# SCH_Endstop_durable.net
KiCad netlist of a schematic drawn in EasyEDA
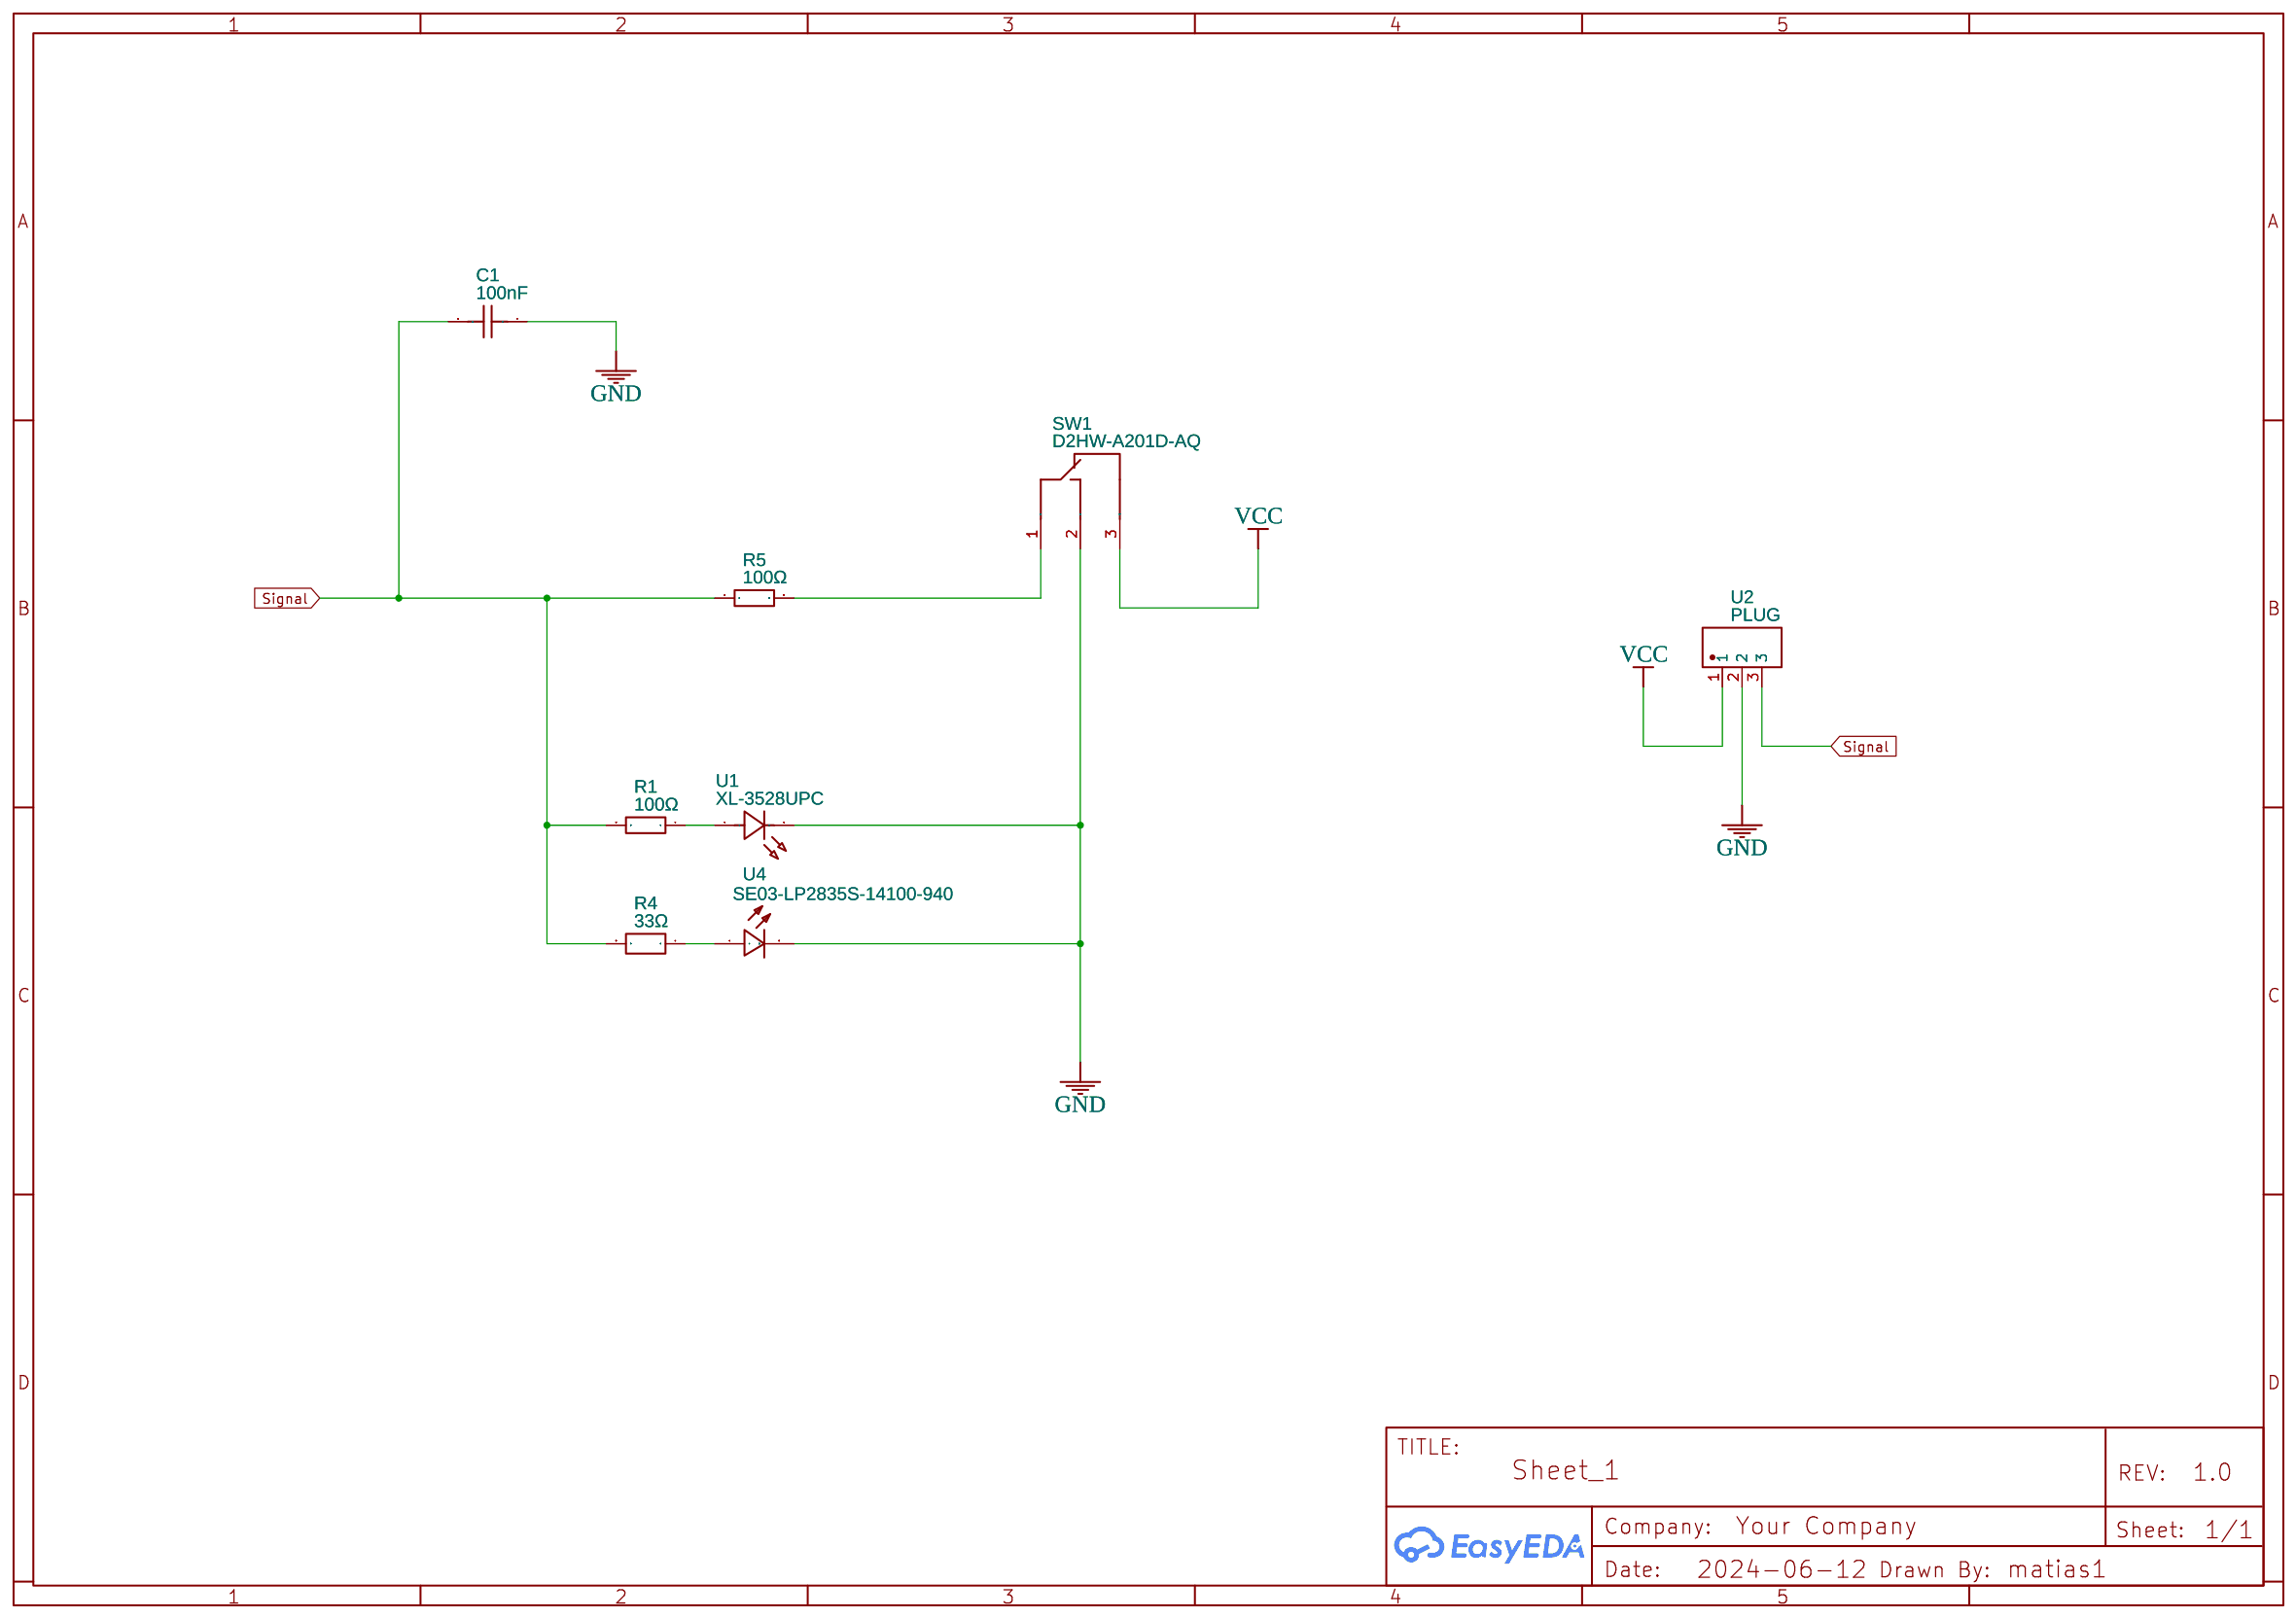
[diagram p0: schematic sheet]

(export (version "E")
  (design (tool "Eeschema 10.0.6"))
  (components
    (comp (ref "C1")
      (value "100nF")
      (fields (field (name "Manufacturer Part") "C1005X7R1C104KT000F") (field (name "Manufacturer") "TDK"))
      (libsource (lib "") (part "C1005X7R1C104KT000F"))
    )
    (comp (ref "R1")
      (value "100Ω")
      (fields (field (name "Manufacturer Part") "AR02BTC1000") (field (name "Manufacturer") "Viking(光颉)"))
      (libsource (lib "") (part "AR02BTC1000_1"))
    )
    (comp (ref "R4")
      (value "33Ω")
      (fields (field (name "Manufacturer Part") "0402 ±5% 33Ω") (field (name "Manufacturer") "VO(翔胜)"))
      (libsource (lib "") (part "0402 ±5% 33Ω"))
    )
    (comp (ref "R5")
      (value "100Ω")
      (fields (field (name "Manufacturer Part") "AR02BTC1000") (field (name "Manufacturer") "Viking(光颉)"))
      (libsource (lib "") (part "AR02BTC1000"))
    )
    (comp (ref "SW1")
      (value "D2HW-A201D-AQ")
      (fields (field (name "Manufacturer") "OMRON(欧姆龙)"))
      (libsource (lib "") (part "D2HW-A201D-AQ"))
    )
    (comp (ref "U1")
      (value "XL-3528UPC")
      (fields (field (name "Manufacturer") "XINGLIGHT(成兴光)"))
      (libsource (lib "") (part "XL-3528UPC"))
    )
    (comp (ref "U2")
      (value "PLUG")
      (fields
        (field (name "Manufacturer Part") "WAFER-XH2.54-3PWZ")
        (field (name "Manufacturer") "XUNPU(讯普)")
      )
      (libsource (lib "") (part "WAFER-XH2.54-3PWZ"))
    )
    (comp (ref "U4")
      (value "SE03-LP2835S-14100-940")
      (fields (field (name "Manufacturer") "XSSY(旭晟)"))
      (libsource (lib "") (part "SE03-LP2835S-14100-940"))
    )
  )
  (nets
    (net (code "1") (name "GND") (class "Default")
      (node (ref "C1") (pin "1") (pinfunction "1_1") (pintype "unspecified"))
      (node (ref "SW1") (pin "2") (pinfunction "2_2") (pintype "unspecified"))
      (node (ref "U1") (pin "2") (pinfunction "K_2") (pintype "unspecified"))
      (node (ref "U2") (pin "2") (pinfunction "2_2") (pintype "unspecified"))
      (node (ref "U4") (pin "2") (pinfunction "C_2") (pintype "unspecified"))
    )
    (net (code "2") (name "Net-(R5-Pad2)") (class "Default")
      (node (ref "R5") (pin "2") (pinfunction "2_2") (pintype "unspecified"))
      (node (ref "SW1") (pin "1") (pinfunction "1_1") (pintype "unspecified"))
    )
    (net (code "3") (name "Net-(U1-A)") (class "Default")
      (node (ref "R1") (pin "1") (pinfunction "1_1") (pintype "unspecified"))
      (node (ref "U1") (pin "1") (pinfunction "A_1") (pintype "unspecified"))
    )
    (net (code "4") (name "Net-(U4-A)") (class "Default")
      (node (ref "R4") (pin "1") (pinfunction "1_1") (pintype "unspecified"))
      (node (ref "U4") (pin "1") (pinfunction "A_1") (pintype "unspecified"))
    )
    (net (code "5") (name "Signal") (class "Default")
      (node (ref "C1") (pin "2") (pinfunction "2_2") (pintype "unspecified"))
      (node (ref "R1") (pin "2") (pinfunction "2_2") (pintype "unspecified"))
      (node (ref "R4") (pin "2") (pinfunction "2_2") (pintype "unspecified"))
      (node (ref "R5") (pin "1") (pinfunction "1_1") (pintype "unspecified"))
      (node (ref "U2") (pin "3") (pinfunction "3_3") (pintype "unspecified"))
    )
    (net (code "6") (name "VCC") (class "Default")
      (node (ref "SW1") (pin "3") (pinfunction "3_3") (pintype "unspecified"))
      (node (ref "U2") (pin "1") (pinfunction "1_1") (pintype "unspecified"))
    )
  )
)
